# Connectors.net
KiCad netlist of a schematic drawn in Altium Designer
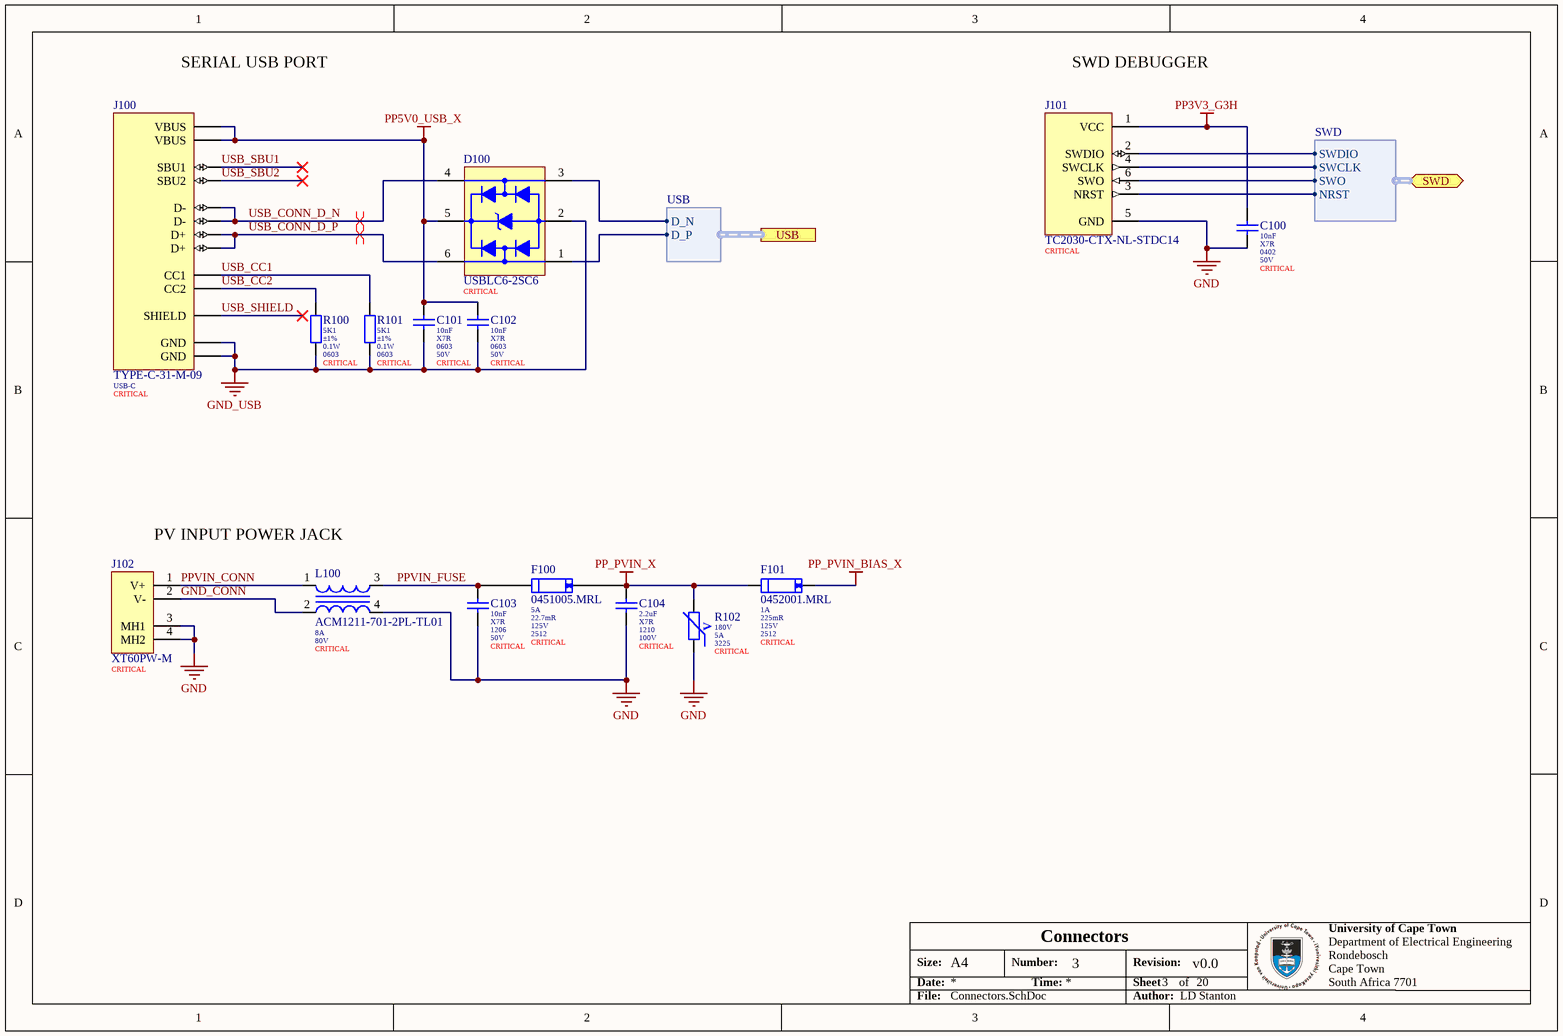
[diagram p0: Connectors.SchDoc]

(export (version "E")
  (design (tool "Eeschema 10.0.6"))
  (components
    (comp (ref "C100")
      (value "10nF")
      (footprint "0402_050_5 (Samsumg) B")
      (description "MLCC 10nF 0402 50V X7R ±10%")
      (fields
        (field (name "DIELECTRIC") "X7R")
        (field (name "PACKAGE") "0402")
        (field (name "VOLTAGE") "50V")
        (field (name "POPULATE") "CRITICAL")
        (field (name "TOLERANCE") "±10%")
        (field (name "LCSC PART NUMBER") "C15195")
      )
      (libsource (lib "University of Cape Town") (part "Symbol"))
    )
    (comp (ref "C101")
      (value "10nF")
      (footprint "0603_080 (Guandong) B")
      (description "MLCC 10nF 0603 50V X7R ±10%")
      (fields
        (field (name "DIELECTRIC") "X7R")
        (field (name "PACKAGE") "0603")
        (field (name "VOLTAGE") "50V")
        (field (name "POPULATE") "CRITICAL")
        (field (name "LCSC PART NUMBER") "C57112")
        (field (name "MANUFACTURER") "Guandong")
      )
      (libsource (lib "University of Cape Town") (part "Symbol"))
    )
    (comp (ref "C102")
      (value "10nF")
      (footprint "0603_080 (Guandong) B")
      (description "MLCC 10nF 0603 50V X7R ±10%")
      (fields
        (field (name "DIELECTRIC") "X7R")
        (field (name "PACKAGE") "0603")
        (field (name "VOLTAGE") "50V")
        (field (name "POPULATE") "CRITICAL")
        (field (name "LCSC PART NUMBER") "C57112")
        (field (name "MANUFACTURER") "Guandong")
      )
      (libsource (lib "University of Cape Town") (part "Symbol"))
    )
    (comp (ref "C103")
      (value "10nF")
      (footprint "1206_125 (Guandong) B")
      (description "MLCC 10nF 1206 50V X7R ±10%")
      (fields
        (field (name "DIELECTRIC") "X7R")
        (field (name "PACKAGE") "1206")
        (field (name "VOLTAGE") "50V")
        (field (name "POPULATE") "CRITICAL")
        (field (name "TOLERANCE") "±10%")
        (field (name "MANUFACTURER") "Guandong")
      )
      (libsource (lib "University of Cape Town") (part "Symbol"))
    )
    (comp (ref "C104")
      (value "2.2uF")
      (footprint "1212_250_J (Samsumg) B")
      (description "MLCC 2.2uF 1210 100V X7R ±10%")
      (fields
        (field (name "DIELECTRIC") "X7R")
        (field (name "PACKAGE") "1210")
        (field (name "VOLTAGE") "100V")
        (field (name "POPULATE") "CRITICAL")
        (field (name "LCSC PART NUMBER") "C55151")
        (field (name "TOLERANCE") "±10%")
      )
      (libsource (lib "University of Cape Town") (part "Symbol"))
    )
    (comp (ref "D100")
      (value "USBLC6-2SC6")
      (footprint "SOT-23-6 (USBLC6-2SC6 ST) B")
      (description "TVS Diode Array Low Capacitance SOT23-6")
      (fields
        (field (name "PLACEMENT") "CRITICAL")
        (field (name "MANUFACTURER") "Tech Public")
        (field (name "LCSC PART NUMBER") "C2827654")
      )
      (libsource (lib "University of Cape Town") (part "STM-USB_DVI_HDMIULC6-4SC6X-SOT23-6L"))
    )
    (comp (ref "F100")
      (value "0451005.MRL")
      (footprint "Littlefuse 45x B")
      (description "Fuse 5A 125VAC/VDCSMD Littlefuse")
      (fields
        (field (name "CURRENT") "5A")
        (field (name "RESISTANCE") "22.7mR")
        (field (name "VOLTAGE") "125V")
        (field (name "PACKAGE") "2512")
        (field (name "PLACEMENT") "CRITICAL")
        (field (name "LCSC PART NUMBER") "C48467")
      )
      (libsource (lib "") (part "Symbol_1"))
    )
    (comp (ref "F101")
      (value "0452001.MRL")
      (footprint "Littlefuse 45x B")
      (description "Fuse 1A 125VAC/VDC SMD Littlefuse")
      (fields
        (field (name "CURRENT") "1A")
        (field (name "RESISTANCE") "225mR")
        (field (name "VOLTAGE") "125V")
        (field (name "PACKAGE") "2512")
        (field (name "PLACEMENT") "CRITICAL")
        (field (name "LCSC PART NUMBER") "C44669")
      )
      (libsource (lib "") (part "Symbol_1"))
    )
    (comp (ref "J100")
      (value "TYPE-C-31-M-09")
      (footprint "TYPE-C-31-M-09_OVH")
      (description "USB Type C Jack USB2.0 SMD/TH")
      (fields
        (field (name "TYPE") "USB-C")
        (field (name "PLACEMENT") "CRITICAL")
        (field (name "LCSC PART NUMBER") "C2689967")
      )
      (libsource (lib "University of Cape Town") (part "TYPE-C-31-M-09"))
    )
    (comp (ref "J101")
      (value "TC2030-CTX-NL-STDC14")
      (footprint "TC2030 NL")
      (description "6-Pin Plug-of-nails connector for SWD")
      (fields (field (name "PLACEMENT") "CRITICAL"))
      (libsource (lib "University of Cape Town") (part "TC2030"))
    )
    (comp (ref "J102")
      (value "XT60PW-M")
      (footprint "XT60-PW_OVH")
      (description "DC Power Connector 500V 30A 0.50mR")
      (fields (field (name "PLACEMENT") "CRITICAL") (field (name "LCSC PART NUMBER") "C98732"))
      (libsource (lib "University of Cape Town") (part "XT60PW-M"))
    )
    (comp (ref "L100")
      (value "ACM1211-701-2PL-TL01")
      (footprint "ACM1211")
      (description "Common Mode Choke 6mR 80V 8A 700R @ 100MHz")
      (fields
        (field (name "CURRENT") "8A")
        (field (name "VOLTAGE") "80V")
        (field (name "PLACEMENT") "CRITICAL")
        (field (name "LCSC PART NUMBER") "C250214")
      )
      (libsource (lib "University of Cape Town") (part "Choke Common Mode"))
    )
    (comp (ref "R100")
      (value "5K1")
      (footprint "0603 (Uniroyal) B")
      (description "Resistor 5K1 0603 ±1% Thick Film Uniroyal")
      (fields
        (field (name "TOLERANCE") "±1%")
        (field (name "POWER") "0.1W")
        (field (name "PACKAGE") "0603")
        (field (name "POPULATE") "CRITICAL")
        (field (name "LCSC PART NUMBER") "C23186")
        (field (name "MANUFACTURER") "Uniroyal")
      )
      (libsource (lib "University of Cape Town") (part "Chip Resistor"))
    )
    (comp (ref "R101")
      (value "5K1")
      (footprint "0603 (Uniroyal) B")
      (description "Resistor 5K1 0603 ±1% Thick Film Uniroyal")
      (fields
        (field (name "TOLERANCE") "±1%")
        (field (name "POWER") "0.1W")
        (field (name "PACKAGE") "0603")
        (field (name "POPULATE") "CRITICAL")
        (field (name "LCSC PART NUMBER") "C23186")
        (field (name "MANUFACTURER") "Uniroyal")
      )
      (libsource (lib "University of Cape Town") (part "Chip Resistor"))
    )
    (comp (ref "R102")
      (value "B72650M0111K072")
      (footprint "3225 (B726) B")
      (description "Varistor MLV 115VAC/150VDC Rated 400A Peak 180V Trigger 3225")
      (fields
        (field (name "VARISTOR VOLTAGE") "180V")
        (field (name "CLAMPING CURRENT") "5A")
        (field (name "PACKAGE") "3225")
        (field (name "PLACEMENT") "CRITICAL")
        (field (name "LCSC PART NUMBER") "C211089")
      )
      (libsource (lib "University of Cape Town") (part "Varistor Nonlinear"))
    )
  )
  (nets
    (net (code "3") (name "/D_N") (class "Default")
      (node (ref "D100") (pin "3") (pinfunction "I/O_2_3") (pintype "passive"))
    )
    (net (code "4") (name "/D_P") (class "Default")
      (node (ref "D100") (pin "1") (pinfunction "I/O_1_1") (pintype "passive"))
    )
    (net (code "5") (name "/GND_CONN") (class "Default")
      (node (ref "J102") (pin "2") (pinfunction "V-_2") (pintype "power_in"))
      (node (ref "L100") (pin "2") (pinfunction "2_2") (pintype "passive"))
    )
    (net (code "6") (name "/NRST") (class "Default")
      (node (ref "J101") (pin "3") (pinfunction "NRST_3") (pintype "output"))
    )
    (net (code "7") (name "/PPVIN_CONN") (class "Default")
      (node (ref "J102") (pin "1") (pinfunction "V+_1") (pintype "power_in"))
      (node (ref "L100") (pin "1") (pinfunction "1_1") (pintype "passive"))
    )
    (net (code "8") (name "/PPVIN_FUSE") (class "Default")
      (node (ref "C103") (pin "1") (pinfunction "1_1") (pintype "passive"))
      (node (ref "F100") (pin "1") (pinfunction "1_1") (pintype "passive"))
      (node (ref "L100") (pin "3") (pinfunction "3_3") (pintype "passive"))
    )
    (net (code "9") (name "/SWCLK") (class "Default")
      (node (ref "J101") (pin "4") (pinfunction "SWCLK_4") (pintype "output"))
    )
    (net (code "10") (name "/SWDIO") (class "Default")
      (node (ref "J101") (pin "2") (pinfunction "SWDIO_2") (pintype "bidirectional"))
    )
    (net (code "11") (name "/SWO") (class "Default")
      (node (ref "J101") (pin "6") (pinfunction "SWO_6") (pintype "input"))
    )
    (net (code "12") (name "/USB_CC1") (class "Default")
      (node (ref "J100") (pin "A5") (pinfunction "CC1_A5") (pintype "passive"))
      (node (ref "R101") (pin "1") (pinfunction "1_1") (pintype "passive"))
    )
    (net (code "13") (name "/USB_CC2") (class "Default")
      (node (ref "J100") (pin "B5") (pinfunction "CC2_B5") (pintype "passive"))
      (node (ref "R100") (pin "1") (pinfunction "1_1") (pintype "passive"))
    )
    (net (code "14") (name "/USB_CONN_D_N") (class "Default")
      (node (ref "D100") (pin "4") (pinfunction "I/O_3_4") (pintype "passive"))
      (node (ref "J100") (pin "A7") (pinfunction "D-_A7") (pintype "bidirectional"))
      (node (ref "J100") (pin "B7") (pinfunction "D-_B7") (pintype "bidirectional"))
    )
    (net (code "15") (name "/USB_CONN_D_P") (class "Default")
      (node (ref "D100") (pin "6") (pinfunction "I/O_4_6") (pintype "passive"))
      (node (ref "J100") (pin "A6") (pinfunction "D+_A6") (pintype "bidirectional"))
      (node (ref "J100") (pin "B6") (pinfunction "D+_B6") (pintype "bidirectional"))
    )
    (net (code "16") (name "/USB_SBU1") (class "Default")
      (node (ref "J100") (pin "A8") (pinfunction "SBU1_A8") (pintype "bidirectional+no_connect"))
    )
    (net (code "17") (name "/USB_SBU2") (class "Default")
      (node (ref "J100") (pin "B8") (pinfunction "SBU2_B8") (pintype "bidirectional+no_connect"))
    )
    (net (code "18") (name "/USB_SHIELD") (class "Default")
      (node (ref "J100") (pin "1") (pinfunction "SHIELD_1") (pintype "passive+no_connect"))
    )
    (net (code "21") (name "GND") (class "Default")
      (node (ref "C100") (pin "2") (pinfunction "2_2") (pintype "passive"))
      (node (ref "C103") (pin "2") (pinfunction "2_2") (pintype "passive"))
      (node (ref "C104") (pin "2") (pinfunction "2_2") (pintype "passive"))
      (node (ref "J101") (pin "5") (pinfunction "GND_5") (pintype "power_in"))
      (node (ref "J102") (pin "3") (pinfunction "MH1_3") (pintype "passive"))
      (node (ref "J102") (pin "4") (pinfunction "MH2_4") (pintype "passive"))
      (node (ref "L100") (pin "4") (pinfunction "4_4") (pintype "passive"))
      (node (ref "R102") (pin "1") (pinfunction "1_1") (pintype "passive"))
    )
    (net (code "22") (name "GND_USB") (class "Default")
      (node (ref "C101") (pin "2") (pinfunction "2_2") (pintype "passive"))
      (node (ref "C102") (pin "2") (pinfunction "2_2") (pintype "passive"))
      (node (ref "D100") (pin "2") (pinfunction "GND_2") (pintype "passive"))
      (node (ref "J100") (pin "A1B12") (pinfunction "GND_A1B12") (pintype "power_in"))
      (node (ref "J100") (pin "B1A12") (pinfunction "GND_B1A12") (pintype "power_in"))
      (node (ref "R100") (pin "2") (pinfunction "2_2") (pintype "passive"))
      (node (ref "R101") (pin "2") (pinfunction "2_2") (pintype "passive"))
    )
    (net (code "23") (name "PP3V3_G3H") (class "Default")
      (node (ref "C100") (pin "1") (pinfunction "1_1") (pintype "passive"))
      (node (ref "J101") (pin "1") (pinfunction "VCC_1") (pintype "power_in"))
    )
    (net (code "24") (name "PP5V0_USB_X") (class "Default")
      (node (ref "C101") (pin "1") (pinfunction "1_1") (pintype "passive"))
      (node (ref "C102") (pin "1") (pinfunction "1_1") (pintype "passive"))
      (node (ref "D100") (pin "5") (pinfunction "VBUS_5") (pintype "passive"))
      (node (ref "J100") (pin "A4B9") (pinfunction "VBUS_A4B9") (pintype "power_in"))
      (node (ref "J100") (pin "B4A9") (pinfunction "VBUS_B4A9") (pintype "power_in"))
    )
    (net (code "25") (name "PP_PVIN_BIAS_X") (class "Default")
      (node (ref "F101") (pin "2") (pinfunction "2_2") (pintype "passive"))
    )
    (net (code "26") (name "PP_PVIN_X") (class "Default")
      (node (ref "C104") (pin "1") (pinfunction "1_1") (pintype "passive"))
      (node (ref "F100") (pin "2") (pinfunction "2_2") (pintype "passive"))
      (node (ref "F101") (pin "1") (pinfunction "1_1") (pintype "passive"))
      (node (ref "R102") (pin "2") (pinfunction "2_2") (pintype "passive"))
    )
  )
)
